# chroma-pcb-nramakri2.net
KiCad netlist of a schematic drawn in EAGLE
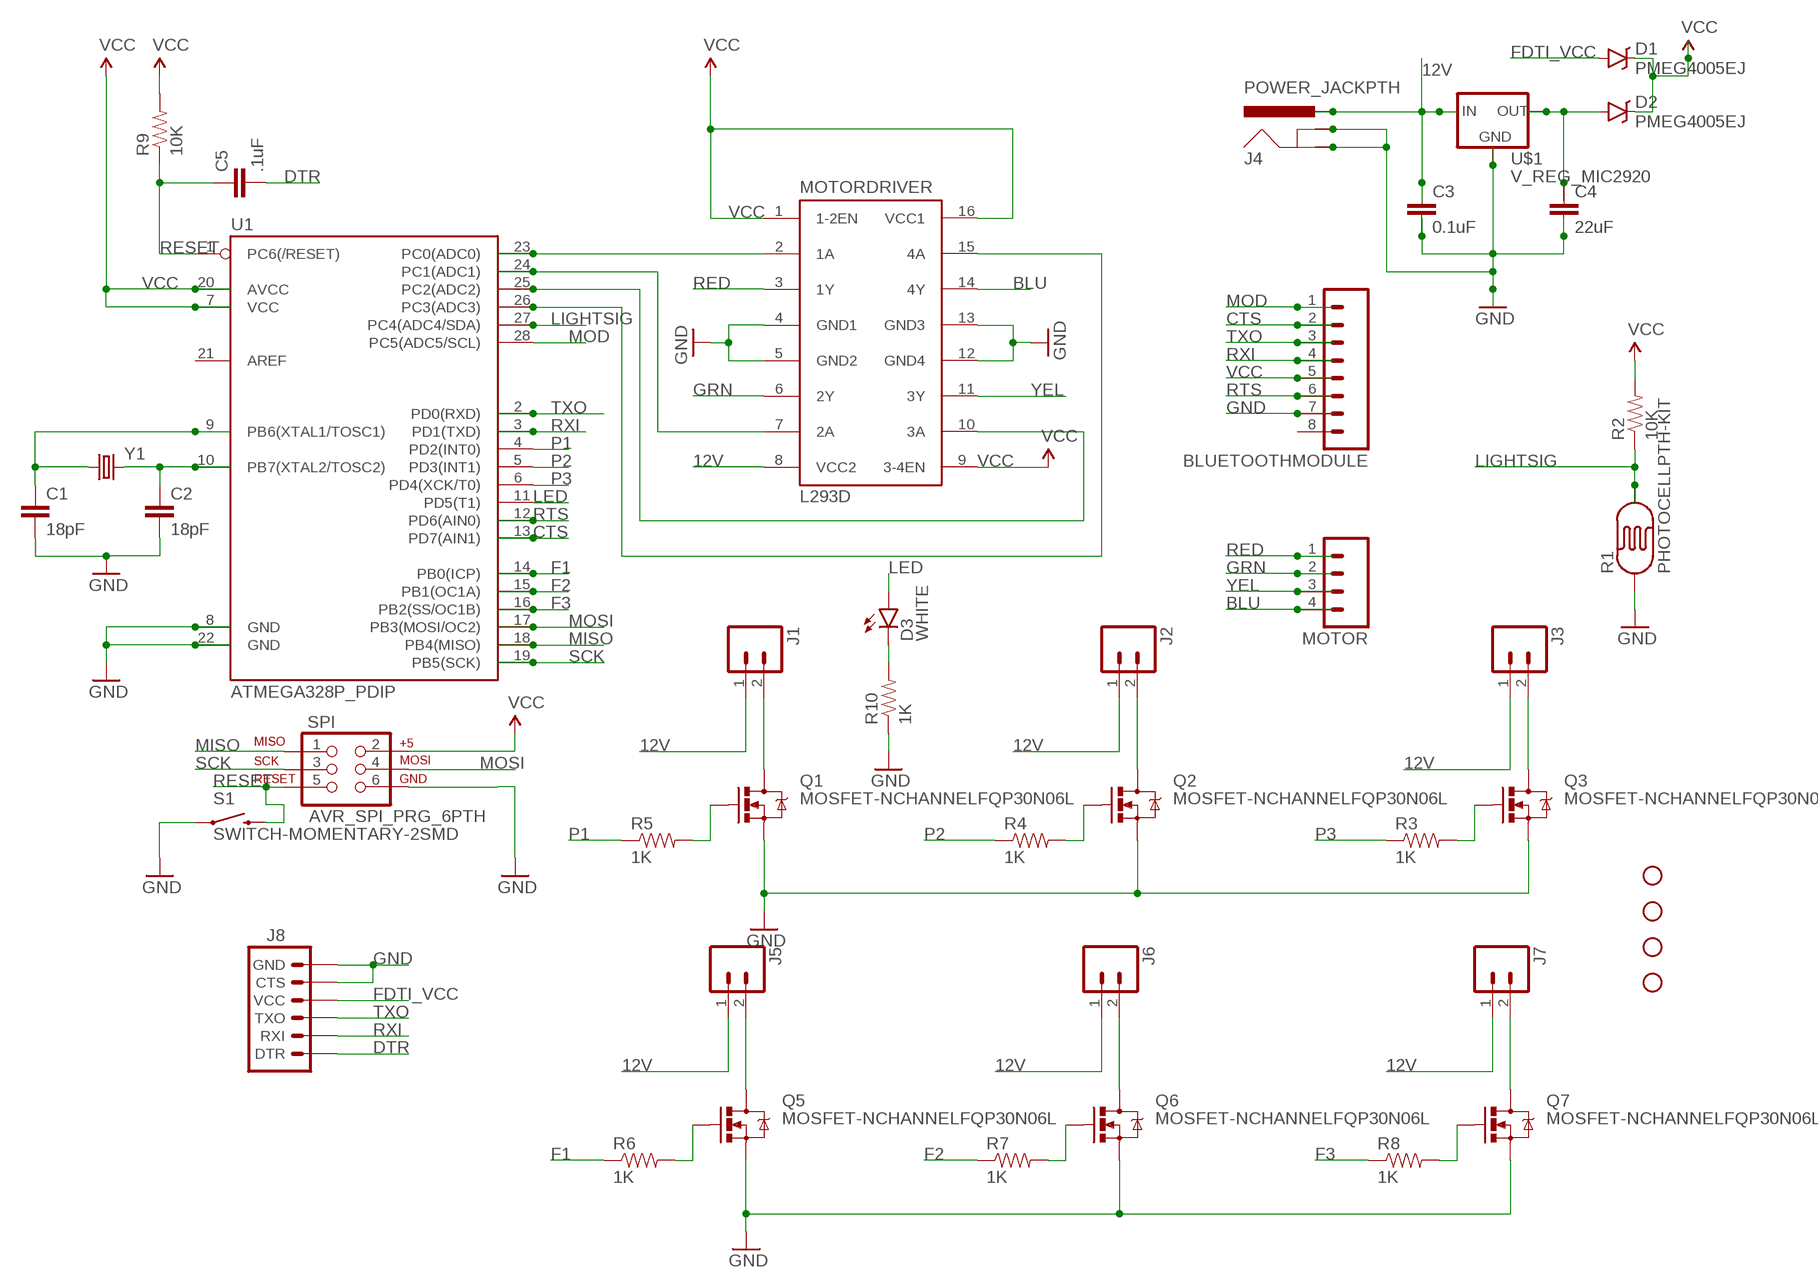
[diagram p0: schematic, sheet 1]

(export (version "E")
  (design (tool "Eeschema 10.0.6"))
  (components
    (comp (ref "BLUETOOTHMODULE")
      (value "M08")
      (footprint "eagle-import:1X08_ROUND")
      (libsource (lib "eagle-import") (part "M08"))
    )
    (comp (ref "C1")
      (value "18pF")
      (footprint "eagle-import:1206")
      (libsource (lib "eagle-import") (part "CAP1206"))
    )
    (comp (ref "C2")
      (value "18pF")
      (footprint "eagle-import:1206")
      (libsource (lib "eagle-import") (part "CAP1206"))
    )
    (comp (ref "C3")
      (value "0.1uF")
      (footprint "eagle-import:1206")
      (libsource (lib "eagle-import") (part "CAP1206"))
    )
    (comp (ref "C4")
      (value "22uF")
      (footprint "eagle-import:1206")
      (libsource (lib "eagle-import") (part "CAP1206"))
    )
    (comp (ref "C5")
      (value ".1uF")
      (footprint "eagle-import:1206")
      (libsource (lib "eagle-import") (part "CAP1206"))
    )
    (comp (ref "D1")
      (value "PMEG4005EJ")
      (footprint "eagle-import:SOD-323")
      (libsource (lib "eagle-import") (part "DIODE-SCHOTTKY-PMEG4005EJ"))
    )
    (comp (ref "D2")
      (value "PMEG4005EJ")
      (footprint "eagle-import:SOD-323")
      (libsource (lib "eagle-import") (part "DIODE-SCHOTTKY-PMEG4005EJ"))
    )
    (comp (ref "D3")
      (value "WHITE")
      (footprint "eagle-import:LED5MM")
      (libsource (lib "eagle-import") (part "LED5MM"))
    )
    (comp (ref "H1")
      (value "STAND-OFF")
      (footprint "eagle-import:STAND-OFF")
      (libsource (lib "eagle-import") (part "STAND-OFF"))
    )
    (comp (ref "H2")
      (value "STAND-OFF")
      (footprint "eagle-import:STAND-OFF")
      (libsource (lib "eagle-import") (part "STAND-OFF"))
    )
    (comp (ref "H3")
      (value "STAND-OFF")
      (footprint "eagle-import:STAND-OFF")
      (libsource (lib "eagle-import") (part "STAND-OFF"))
    )
    (comp (ref "H4")
      (value "STAND-OFF")
      (footprint "eagle-import:STAND-OFF")
      (libsource (lib "eagle-import") (part "STAND-OFF"))
    )
    (comp (ref "J1")
      (value "M023.5MM")
      (footprint "eagle-import:SCREWTERMINAL-3.5MM-2")
      (libsource (lib "eagle-import") (part "M023.5MM"))
    )
    (comp (ref "J2")
      (value "M023.5MM")
      (footprint "eagle-import:SCREWTERMINAL-3.5MM-2")
      (libsource (lib "eagle-import") (part "M023.5MM"))
    )
    (comp (ref "J3")
      (value "M023.5MM")
      (footprint "eagle-import:SCREWTERMINAL-3.5MM-2")
      (libsource (lib "eagle-import") (part "M023.5MM"))
    )
    (comp (ref "J4")
      (value "POWER_JACKPTH")
      (footprint "eagle-import:POWER_JACK_PTH")
      (libsource (lib "eagle-import") (part "POWER_JACKPTH"))
    )
    (comp (ref "J5")
      (value "M023.5MM")
      (footprint "eagle-import:SCREWTERMINAL-3.5MM-2")
      (libsource (lib "eagle-import") (part "M023.5MM"))
    )
    (comp (ref "J6")
      (value "M023.5MM")
      (footprint "eagle-import:SCREWTERMINAL-3.5MM-2")
      (libsource (lib "eagle-import") (part "M023.5MM"))
    )
    (comp (ref "J7")
      (value "M023.5MM")
      (footprint "eagle-import:SCREWTERMINAL-3.5MM-2")
      (libsource (lib "eagle-import") (part "M023.5MM"))
    )
    (comp (ref "J8")
      (value "ARDUINO_SERIAL_PROGRAMPTH")
      (footprint "eagle-import:1X06")
      (libsource (lib "eagle-import") (part "ARDUINO_SERIAL_PROGRAMPTH"))
    )
    (comp (ref "MOTOR")
      (value "M04PTH")
      (footprint "eagle-import:1X04")
      (libsource (lib "eagle-import") (part "M04PTH"))
    )
    (comp (ref "MOTORDRIVER")
      (value "L293D")
      (footprint "eagle-import:DIL16")
      (libsource (lib "eagle-import") (part "L293D"))
    )
    (comp (ref "Q1")
      (value "MOSFET-NCHANNELFQP30N06L")
      (footprint "eagle-import:TO220V")
      (libsource (lib "eagle-import") (part "MOSFET-NCHANNELFQP30N06L"))
    )
    (comp (ref "Q2")
      (value "MOSFET-NCHANNELFQP30N06L")
      (footprint "eagle-import:TO220V")
      (libsource (lib "eagle-import") (part "MOSFET-NCHANNELFQP30N06L"))
    )
    (comp (ref "Q3")
      (value "MOSFET-NCHANNELFQP30N06L")
      (footprint "eagle-import:TO220V")
      (libsource (lib "eagle-import") (part "MOSFET-NCHANNELFQP30N06L"))
    )
    (comp (ref "Q5")
      (value "MOSFET-NCHANNELFQP30N06L")
      (footprint "eagle-import:TO220V")
      (libsource (lib "eagle-import") (part "MOSFET-NCHANNELFQP30N06L"))
    )
    (comp (ref "Q6")
      (value "MOSFET-NCHANNELFQP30N06L")
      (footprint "eagle-import:TO220V")
      (libsource (lib "eagle-import") (part "MOSFET-NCHANNELFQP30N06L"))
    )
    (comp (ref "Q7")
      (value "MOSFET-NCHANNELFQP30N06L")
      (footprint "eagle-import:TO220V")
      (libsource (lib "eagle-import") (part "MOSFET-NCHANNELFQP30N06L"))
    )
    (comp (ref "R1")
      (value "PHOTOCELLPTH-KIT")
      (footprint "eagle-import:PHOTOCELL-KIT")
      (libsource (lib "eagle-import") (part "PHOTOCELLPTH-KIT"))
    )
    (comp (ref "R2")
      (value "10K")
      (footprint "eagle-import:1206")
      (libsource (lib "eagle-import") (part "RESISTOR1206"))
    )
    (comp (ref "R3")
      (value "1K")
      (footprint "eagle-import:1206")
      (libsource (lib "eagle-import") (part "RESISTOR1206"))
    )
    (comp (ref "R4")
      (value "1K")
      (footprint "eagle-import:1206")
      (libsource (lib "eagle-import") (part "RESISTOR1206"))
    )
    (comp (ref "R5")
      (value "1K")
      (footprint "eagle-import:1206")
      (libsource (lib "eagle-import") (part "RESISTOR1206"))
    )
    (comp (ref "R6")
      (value "1K")
      (footprint "eagle-import:1206")
      (libsource (lib "eagle-import") (part "RESISTOR1206"))
    )
    (comp (ref "R7")
      (value "1K")
      (footprint "eagle-import:1206")
      (libsource (lib "eagle-import") (part "RESISTOR1206"))
    )
    (comp (ref "R8")
      (value "1K")
      (footprint "eagle-import:1206")
      (libsource (lib "eagle-import") (part "RESISTOR1206"))
    )
    (comp (ref "R9")
      (value "10K")
      (footprint "eagle-import:1206")
      (libsource (lib "eagle-import") (part "RESISTOR1206"))
    )
    (comp (ref "R10")
      (value "1K")
      (footprint "eagle-import:1206")
      (libsource (lib "eagle-import") (part "RESISTOR1206"))
    )
    (comp (ref "S1")
      (value "SWITCH-MOMENTARY-2SMD")
      (footprint "eagle-import:TACTILE-SWITCH-SMD")
      (libsource (lib "eagle-import") (part "SWITCH-MOMENTARY-2SMD"))
    )
    (comp (ref "SPI")
      (value "AVR_SPI_PRG_6PTH")
      (footprint "eagle-import:2X3")
      (libsource (lib "eagle-import") (part "AVR_SPI_PRG_6PTH"))
    )
    (comp (ref "U$1")
      (value "V_REG_MIC2920")
      (footprint "eagle-import:SOT223")
      (libsource (lib "eagle-import") (part "V_REG_MIC2920"))
    )
    (comp (ref "U1")
      (value "ATMEGA328P_PDIP")
      (footprint "eagle-import:DIL28-3")
      (libsource (lib "eagle-import") (part "ATMEGA328P_PDIP"))
    )
    (comp (ref "Y1")
      (value "CRYSTALTXC-7A")
      (footprint "eagle-import:CRYSTAL-TXC-7A")
      (libsource (lib "eagle-import") (part "CRYSTALTXC-7A"))
    )
  )
  (nets
    (net (code "1") (name "/12V") (class "Default")
      (node (ref "C3") (pin "1") (pinfunction "1_1") (pintype "passive"))
      (node (ref "J1") (pin "1") (pinfunction "1_1") (pintype "passive"))
      (node (ref "J2") (pin "1") (pinfunction "1_1") (pintype "passive"))
      (node (ref "J3") (pin "1") (pinfunction "1_1") (pintype "passive"))
      (node (ref "J4") (pin "PWR") (pinfunction "PWR_PWR") (pintype "bidirectional"))
      (node (ref "J5") (pin "1") (pinfunction "1_1") (pintype "passive"))
      (node (ref "J6") (pin "1") (pinfunction "1_1") (pintype "passive"))
      (node (ref "J7") (pin "1") (pinfunction "1_1") (pintype "passive"))
      (node (ref "MOTORDRIVER") (pin "8") (pinfunction "VCC2_8") (pintype "power_in"))
      (node (ref "U$1") (pin "1") (pinfunction "IN_1") (pintype "input"))
    )
    (net (code "2") (name "/BLU") (class "Default")
      (node (ref "MOTOR") (pin "4") (pinfunction "4_4") (pintype "passive"))
      (node (ref "MOTORDRIVER") (pin "14") (pinfunction "4Y_14") (pintype "output"))
    )
    (net (code "3") (name "/CTS") (class "Default")
      (node (ref "BLUETOOTHMODULE") (pin "2") (pinfunction "2_2") (pintype "passive"))
      (node (ref "U1") (pin "13") (pinfunction "PD7(AIN1)_13") (pintype "bidirectional"))
    )
    (net (code "4") (name "/DTR") (class "Default")
      (node (ref "C5") (pin "2") (pinfunction "2_2") (pintype "passive"))
      (node (ref "J8") (pin "1") (pinfunction "DTR_1") (pintype "passive"))
    )
    (net (code "5") (name "/F1") (class "Default")
      (node (ref "R6") (pin "1") (pinfunction "1_1") (pintype "passive"))
      (node (ref "U1") (pin "14") (pinfunction "PB0(ICP)_14") (pintype "bidirectional"))
    )
    (net (code "6") (name "/F2") (class "Default")
      (node (ref "R7") (pin "1") (pinfunction "1_1") (pintype "passive"))
      (node (ref "U1") (pin "15") (pinfunction "PB1(OC1A)_15") (pintype "bidirectional"))
    )
    (net (code "7") (name "/F3") (class "Default")
      (node (ref "R8") (pin "1") (pinfunction "1_1") (pintype "passive"))
      (node (ref "U1") (pin "16") (pinfunction "PB2(SS/OC1B)_16") (pintype "bidirectional"))
    )
    (net (code "8") (name "/FDTI_VCC") (class "Default")
      (node (ref "D1") (pin "A") (pinfunction "A_A") (pintype "passive"))
      (node (ref "J8") (pin "4") (pinfunction "VCC_4") (pintype "passive"))
    )
    (net (code "9") (name "/GRN") (class "Default")
      (node (ref "MOTOR") (pin "2") (pinfunction "2_2") (pintype "passive"))
      (node (ref "MOTORDRIVER") (pin "6") (pinfunction "2Y_6") (pintype "output"))
    )
    (net (code "10") (name "/LED") (class "Default")
      (node (ref "D3") (pin "A") (pinfunction "A_A") (pintype "passive"))
      (node (ref "U1") (pin "11") (pinfunction "PD5(T1)_11") (pintype "bidirectional"))
    )
    (net (code "11") (name "/LIGHTSIG") (class "Default")
      (node (ref "R1") (pin "2") (pinfunction "P$2_2") (pintype "bidirectional"))
      (node (ref "R2") (pin "1") (pinfunction "1_1") (pintype "passive"))
      (node (ref "U1") (pin "27") (pinfunction "PC4(ADC4/SDA)_27") (pintype "bidirectional"))
    )
    (net (code "12") (name "/MISO") (class "Default")
      (node (ref "SPI") (pin "1") (pinfunction "1_1") (pintype "passive"))
      (node (ref "U1") (pin "18") (pinfunction "PB4(MISO)_18") (pintype "bidirectional"))
    )
    (net (code "13") (name "/MOD") (class "Default")
      (node (ref "BLUETOOTHMODULE") (pin "1") (pinfunction "1_1") (pintype "passive"))
      (node (ref "U1") (pin "28") (pinfunction "PC5(ADC5/SCL)_28") (pintype "bidirectional"))
    )
    (net (code "14") (name "/MOSI") (class "Default")
      (node (ref "SPI") (pin "4") (pinfunction "4_4") (pintype "passive"))
      (node (ref "U1") (pin "17") (pinfunction "PB3(MOSI/OC2)_17") (pintype "bidirectional"))
    )
    (net (code "15") (name "/P1") (class "Default")
      (node (ref "R5") (pin "1") (pinfunction "1_1") (pintype "passive"))
      (node (ref "U1") (pin "4") (pinfunction "PD2(INT0)_4") (pintype "bidirectional"))
    )
    (net (code "16") (name "/P2") (class "Default")
      (node (ref "R4") (pin "1") (pinfunction "1_1") (pintype "passive"))
      (node (ref "U1") (pin "5") (pinfunction "PD3(INT1)_5") (pintype "bidirectional"))
    )
    (net (code "17") (name "/P3") (class "Default")
      (node (ref "R3") (pin "1") (pinfunction "1_1") (pintype "passive"))
      (node (ref "U1") (pin "6") (pinfunction "PD4(XCK/T0)_6") (pintype "bidirectional"))
    )
    (net (code "18") (name "/RED") (class "Default")
      (node (ref "MOTOR") (pin "1") (pinfunction "1_1") (pintype "passive"))
      (node (ref "MOTORDRIVER") (pin "3") (pinfunction "1Y_3") (pintype "output"))
    )
    (net (code "19") (name "/RESET") (class "Default")
      (node (ref "C5") (pin "1") (pinfunction "1_1") (pintype "passive"))
      (node (ref "R9") (pin "1") (pinfunction "1_1") (pintype "passive"))
      (node (ref "S1") (pin "3") (pinfunction "2_3") (pintype "passive"))
      (node (ref "SPI") (pin "5") (pinfunction "5_5") (pintype "passive"))
      (node (ref "U1") (pin "1") (pinfunction "PC6(/RESET)_1") (pintype "bidirectional"))
    )
    (net (code "20") (name "/RTS") (class "Default")
      (node (ref "BLUETOOTHMODULE") (pin "6") (pinfunction "6_6") (pintype "passive"))
      (node (ref "U1") (pin "12") (pinfunction "PD6(AIN0)_12") (pintype "bidirectional"))
    )
    (net (code "21") (name "/RXI") (class "Default")
      (node (ref "BLUETOOTHMODULE") (pin "4") (pinfunction "4_4") (pintype "passive"))
      (node (ref "J8") (pin "2") (pinfunction "RXI_2") (pintype "passive"))
      (node (ref "U1") (pin "3") (pinfunction "PD1(TXD)_3") (pintype "bidirectional"))
    )
    (net (code "22") (name "/SCK") (class "Default")
      (node (ref "SPI") (pin "3") (pinfunction "3_3") (pintype "passive"))
      (node (ref "U1") (pin "19") (pinfunction "PB5(SCK)_19") (pintype "bidirectional"))
    )
    (net (code "23") (name "/TXO") (class "Default")
      (node (ref "BLUETOOTHMODULE") (pin "3") (pinfunction "3_3") (pintype "passive"))
      (node (ref "J8") (pin "3") (pinfunction "TXO_3") (pintype "passive"))
      (node (ref "U1") (pin "2") (pinfunction "PD0(RXD)_2") (pintype "bidirectional"))
    )
    (net (code "24") (name "/YEL") (class "Default")
      (node (ref "MOTOR") (pin "3") (pinfunction "3_3") (pintype "passive"))
      (node (ref "MOTORDRIVER") (pin "11") (pinfunction "3Y_11") (pintype "output"))
    )
    (net (code "25") (name "GND") (class "Default")
      (node (ref "BLUETOOTHMODULE") (pin "7") (pinfunction "7_7") (pintype "passive"))
      (node (ref "C1") (pin "2") (pinfunction "2_2") (pintype "passive"))
      (node (ref "C2") (pin "2") (pinfunction "2_2") (pintype "passive"))
      (node (ref "C3") (pin "2") (pinfunction "2_2") (pintype "passive"))
      (node (ref "C4") (pin "2") (pinfunction "2_2") (pintype "passive"))
      (node (ref "J4") (pin "GND") (pinfunction "GND_GND") (pintype "bidirectional"))
      (node (ref "J4") (pin "GNDBREAK") (pinfunction "GNDBREAK_GNDBREAK") (pintype "bidirectional"))
      (node (ref "J8") (pin "5") (pinfunction "CTS_5") (pintype "passive"))
      (node (ref "J8") (pin "6") (pinfunction "GND_6") (pintype "passive"))
      (node (ref "MOTORDRIVER") (pin "12") (pinfunction "GND4_12") (pintype "power_in"))
      (node (ref "MOTORDRIVER") (pin "13") (pinfunction "GND3_13") (pintype "power_in"))
      (node (ref "MOTORDRIVER") (pin "4") (pinfunction "GND1_4") (pintype "power_in"))
      (node (ref "MOTORDRIVER") (pin "5") (pinfunction "GND2_5") (pintype "power_in"))
      (node (ref "Q1") (pin "3") (pinfunction "S_3") (pintype "passive"))
      (node (ref "Q2") (pin "3") (pinfunction "S_3") (pintype "passive"))
      (node (ref "Q3") (pin "3") (pinfunction "S_3") (pintype "passive"))
      (node (ref "Q5") (pin "3") (pinfunction "S_3") (pintype "passive"))
      (node (ref "Q6") (pin "3") (pinfunction "S_3") (pintype "passive"))
      (node (ref "Q7") (pin "3") (pinfunction "S_3") (pintype "passive"))
      (node (ref "R1") (pin "1") (pinfunction "P$1_1") (pintype "bidirectional"))
      (node (ref "R10") (pin "1") (pinfunction "1_1") (pintype "passive"))
      (node (ref "S1") (pin "1") (pinfunction "1_1") (pintype "passive"))
      (node (ref "SPI") (pin "6") (pinfunction "6_6") (pintype "passive"))
      (node (ref "U$1") (pin "2") (pinfunction "GND_2") (pintype "input"))
      (node (ref "U1") (pin "22") (pinfunction "GND_22") (pintype "bidirectional"))
      (node (ref "U1") (pin "8") (pinfunction "GND_8") (pintype "bidirectional"))
    )
    (net (code "26") (name "Net-(D3-C)") (class "Default")
      (node (ref "D3") (pin "K") (pinfunction "C_K") (pintype "passive"))
      (node (ref "R10") (pin "2") (pinfunction "2_2") (pintype "passive"))
    )
    (net (code "27") (name "Net-(MOTORDRIVER-1A)") (class "Default")
      (node (ref "MOTORDRIVER") (pin "2") (pinfunction "1A_2") (pintype "input"))
      (node (ref "U1") (pin "23") (pinfunction "PC0(ADC0)_23") (pintype "bidirectional"))
    )
    (net (code "28") (name "Net-(MOTORDRIVER-2A)") (class "Default")
      (node (ref "MOTORDRIVER") (pin "7") (pinfunction "2A_7") (pintype "input"))
      (node (ref "U1") (pin "24") (pinfunction "PC1(ADC1)_24") (pintype "bidirectional"))
    )
    (net (code "29") (name "Net-(MOTORDRIVER-3A)") (class "Default")
      (node (ref "MOTORDRIVER") (pin "10") (pinfunction "3A_10") (pintype "input"))
      (node (ref "U1") (pin "25") (pinfunction "PC2(ADC2)_25") (pintype "bidirectional"))
    )
    (net (code "30") (name "Net-(MOTORDRIVER-4A)") (class "Default")
      (node (ref "MOTORDRIVER") (pin "15") (pinfunction "4A_15") (pintype "input"))
      (node (ref "U1") (pin "26") (pinfunction "PC3(ADC3)_26") (pintype "bidirectional"))
    )
    (net (code "31") (name "Net-(Q1-D)") (class "Default")
      (node (ref "J1") (pin "2") (pinfunction "2_2") (pintype "passive"))
      (node (ref "Q1") (pin "2") (pinfunction "D_2") (pintype "passive"))
    )
    (net (code "32") (name "Net-(Q1-G)") (class "Default")
      (node (ref "Q1") (pin "1") (pinfunction "G_1") (pintype "passive"))
      (node (ref "R5") (pin "2") (pinfunction "2_2") (pintype "passive"))
    )
    (net (code "33") (name "Net-(Q2-D)") (class "Default")
      (node (ref "J2") (pin "2") (pinfunction "2_2") (pintype "passive"))
      (node (ref "Q2") (pin "2") (pinfunction "D_2") (pintype "passive"))
    )
    (net (code "34") (name "Net-(Q2-G)") (class "Default")
      (node (ref "Q2") (pin "1") (pinfunction "G_1") (pintype "passive"))
      (node (ref "R4") (pin "2") (pinfunction "2_2") (pintype "passive"))
    )
    (net (code "35") (name "Net-(Q3-D)") (class "Default")
      (node (ref "J3") (pin "2") (pinfunction "2_2") (pintype "passive"))
      (node (ref "Q3") (pin "2") (pinfunction "D_2") (pintype "passive"))
    )
    (net (code "36") (name "Net-(Q3-G)") (class "Default")
      (node (ref "Q3") (pin "1") (pinfunction "G_1") (pintype "passive"))
      (node (ref "R3") (pin "2") (pinfunction "2_2") (pintype "passive"))
    )
    (net (code "37") (name "Net-(Q5-D)") (class "Default")
      (node (ref "J5") (pin "2") (pinfunction "2_2") (pintype "passive"))
      (node (ref "Q5") (pin "2") (pinfunction "D_2") (pintype "passive"))
    )
    (net (code "38") (name "Net-(Q5-G)") (class "Default")
      (node (ref "Q5") (pin "1") (pinfunction "G_1") (pintype "passive"))
      (node (ref "R6") (pin "2") (pinfunction "2_2") (pintype "passive"))
    )
    (net (code "39") (name "Net-(Q6-D)") (class "Default")
      (node (ref "J6") (pin "2") (pinfunction "2_2") (pintype "passive"))
      (node (ref "Q6") (pin "2") (pinfunction "D_2") (pintype "passive"))
    )
    (net (code "40") (name "Net-(Q6-G)") (class "Default")
      (node (ref "Q6") (pin "1") (pinfunction "G_1") (pintype "passive"))
      (node (ref "R7") (pin "2") (pinfunction "2_2") (pintype "passive"))
    )
    (net (code "41") (name "Net-(Q7-D)") (class "Default")
      (node (ref "J7") (pin "2") (pinfunction "2_2") (pintype "passive"))
      (node (ref "Q7") (pin "2") (pinfunction "D_2") (pintype "passive"))
    )
    (net (code "42") (name "Net-(Q7-G)") (class "Default")
      (node (ref "Q7") (pin "1") (pinfunction "G_1") (pintype "passive"))
      (node (ref "R8") (pin "2") (pinfunction "2_2") (pintype "passive"))
    )
    (net (code "43") (name "Net-(U$1-OUT)") (class "Default")
      (node (ref "C4") (pin "1") (pinfunction "1_1") (pintype "passive"))
      (node (ref "D2") (pin "A") (pinfunction "A_A") (pintype "passive"))
      (node (ref "U$1") (pin "3") (pinfunction "OUT_3") (pintype "passive"))
    )
    (net (code "44") (name "Net-(U1-PB6(XTAL1{slash}TOSC1))") (class "Default")
      (node (ref "C1") (pin "1") (pinfunction "1_1") (pintype "passive"))
      (node (ref "U1") (pin "9") (pinfunction "PB6(XTAL1/TOSC1)_9") (pintype "bidirectional"))
      (node (ref "Y1") (pin "P$1") (pinfunction "1_P$1") (pintype "passive"))
    )
    (net (code "45") (name "Net-(U1-PB7(XTAL2{slash}TOSC2))") (class "Default")
      (node (ref "C2") (pin "1") (pinfunction "1_1") (pintype "passive"))
      (node (ref "U1") (pin "10") (pinfunction "PB7(XTAL2/TOSC2)_10") (pintype "bidirectional"))
      (node (ref "Y1") (pin "P$2") (pinfunction "2_P$2") (pintype "passive"))
    )
    (net (code "46") (name "VCC") (class "Default")
      (node (ref "BLUETOOTHMODULE") (pin "5") (pinfunction "5_5") (pintype "passive"))
      (node (ref "D1") (pin "C") (pinfunction "C_C") (pintype "passive"))
      (node (ref "D2") (pin "C") (pinfunction "C_C") (pintype "passive"))
      (node (ref "MOTORDRIVER") (pin "1") (pinfunction "1-2EN_1") (pintype "input"))
      (node (ref "MOTORDRIVER") (pin "16") (pinfunction "VCC1_16") (pintype "power_in"))
      (node (ref "MOTORDRIVER") (pin "9") (pinfunction "3-4EN_9") (pintype "input"))
      (node (ref "R2") (pin "2") (pinfunction "2_2") (pintype "passive"))
      (node (ref "R9") (pin "2") (pinfunction "2_2") (pintype "passive"))
      (node (ref "SPI") (pin "2") (pinfunction "2_2") (pintype "passive"))
      (node (ref "U1") (pin "20") (pinfunction "AVCC_20") (pintype "bidirectional"))
      (node (ref "U1") (pin "7") (pinfunction "VCC_7") (pintype "bidirectional"))
    )
    (net (code "47") (name "unconnected-(BLUETOOTHMODULE-Pad8)") (class "Default")
      (node (ref "BLUETOOTHMODULE") (pin "8") (pinfunction "8_8") (pintype "passive"))
    )
    (net (code "48") (name "unconnected-(U1-AREF-Pad21)") (class "Default")
      (node (ref "U1") (pin "21") (pinfunction "AREF_21") (pintype "bidirectional"))
    )
  )
)
